# VCA-R2.net
KiCad netlist of a schematic drawn in EAGLE
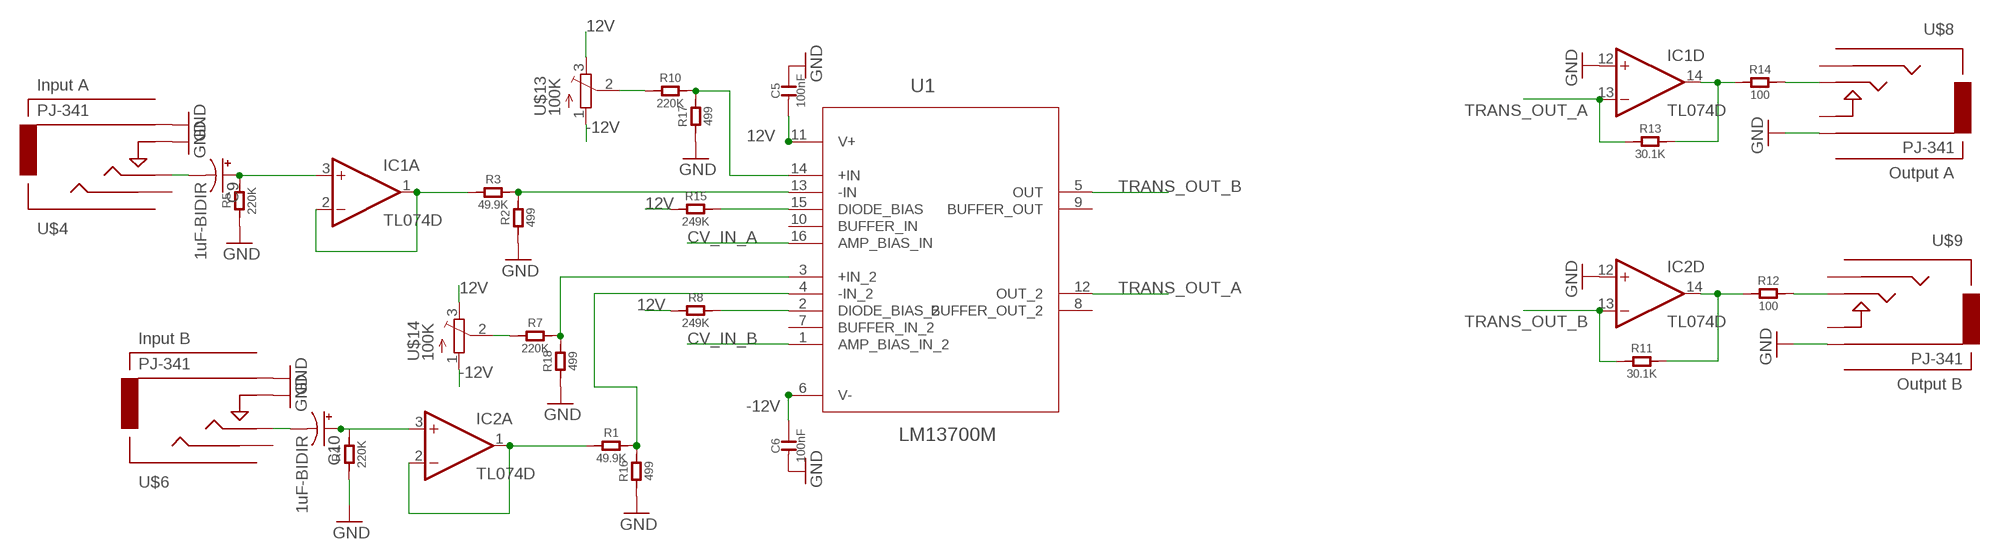
[diagram p0: schematic, sheet 1, part 1 of 2]
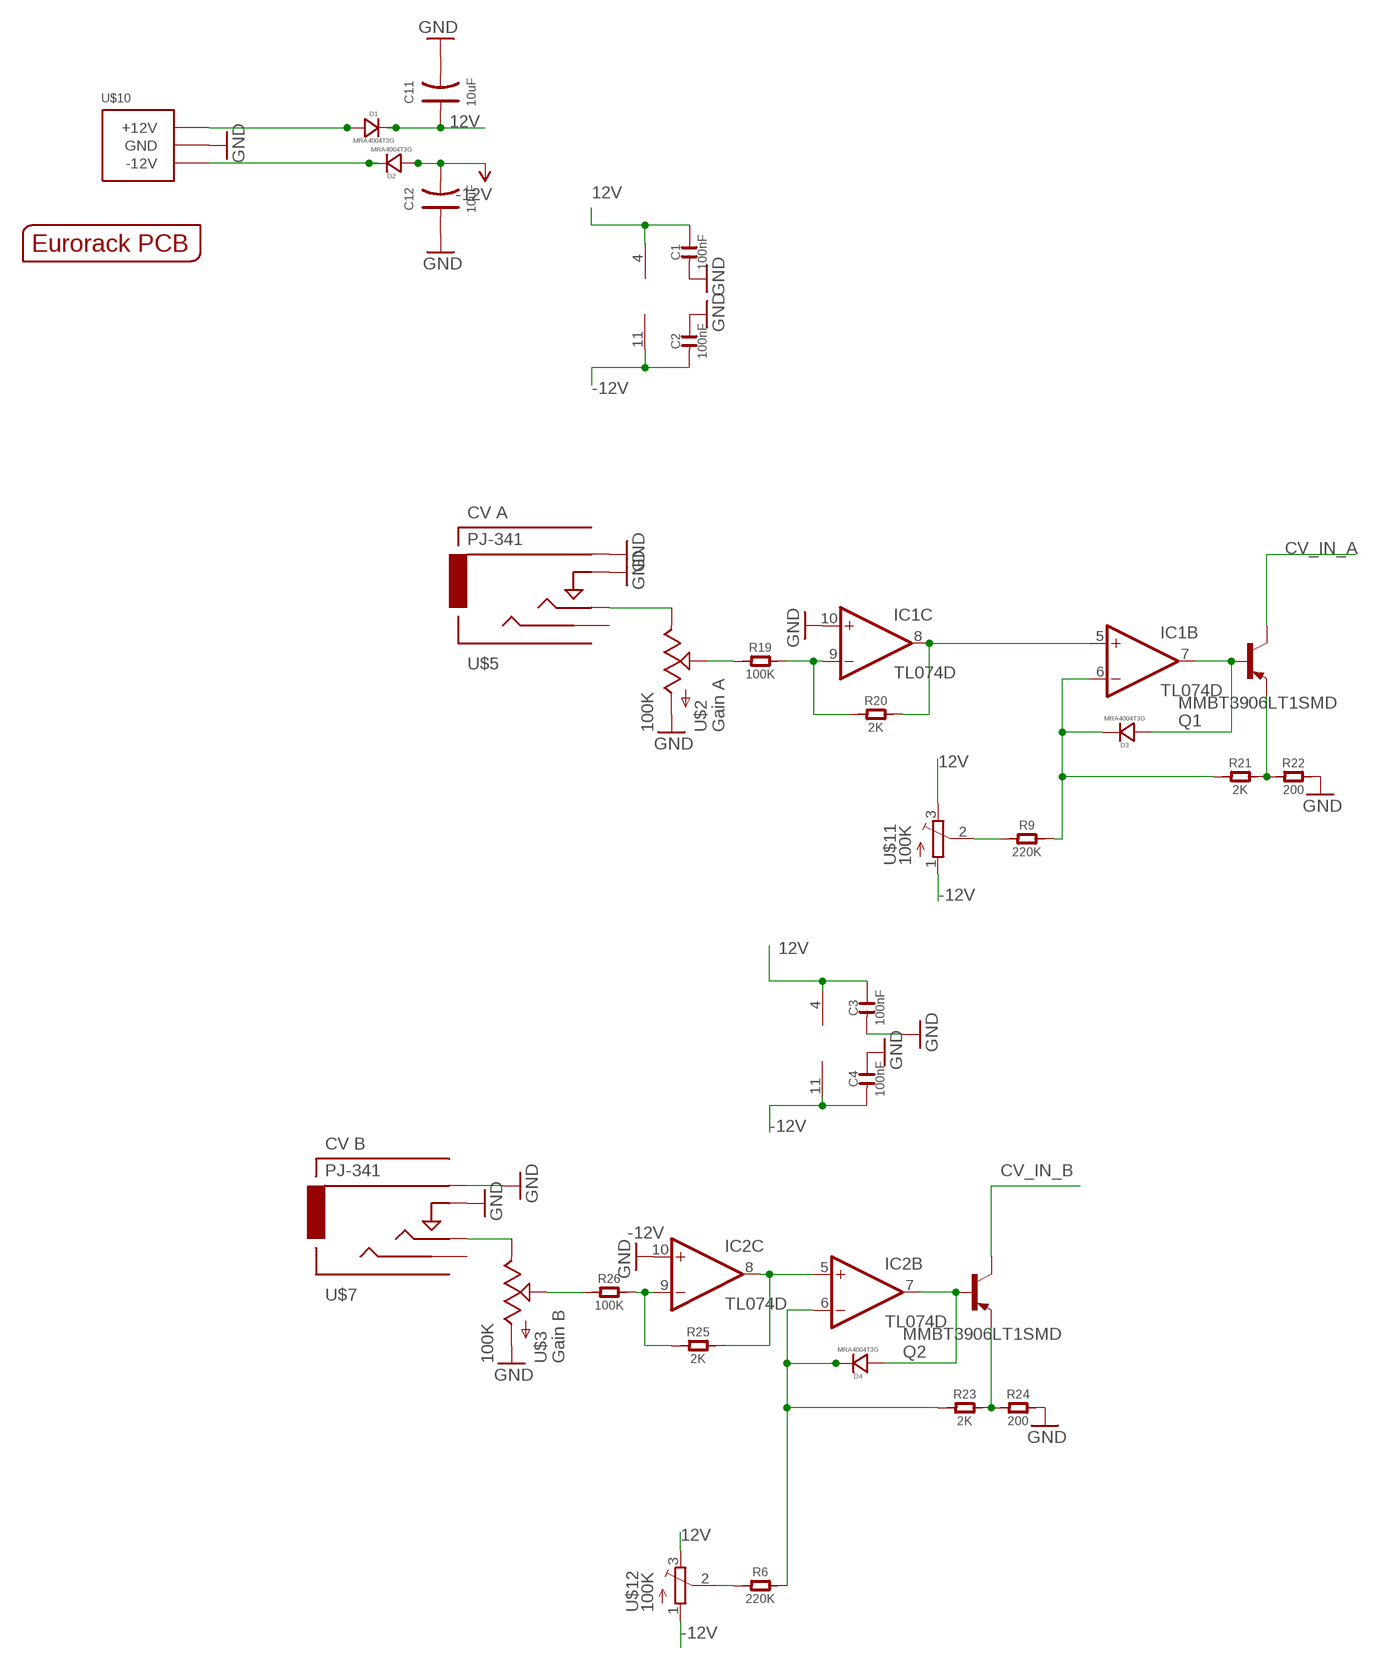
[diagram p1: schematic, sheet 1, part 2 of 2]

(export (version "E")
  (design (tool "Eeschema 10.0.6"))
  (components
    (comp (ref "C1")
      (value "100nF")
      (footprint "eagle-import:C0603")
      (libsource (lib "eagle-import") (part "C-0603"))
    )
    (comp (ref "C2")
      (value "100nF")
      (footprint "eagle-import:C0603")
      (libsource (lib "eagle-import") (part "C-0603"))
    )
    (comp (ref "C3")
      (value "100nF")
      (footprint "eagle-import:C0603")
      (libsource (lib "eagle-import") (part "C-0603"))
    )
    (comp (ref "C4")
      (value "100nF")
      (footprint "eagle-import:C0603")
      (libsource (lib "eagle-import") (part "C-0603"))
    )
    (comp (ref "C5")
      (value "100nF")
      (footprint "eagle-import:C0603")
      (libsource (lib "eagle-import") (part "C-0603"))
    )
    (comp (ref "C6")
      (value "100nF")
      (footprint "eagle-import:C0603")
      (libsource (lib "eagle-import") (part "C-0603"))
    )
    (comp (ref "C9")
      (value "1uF-BIDIR")
      (footprint "eagle-import:153CLV-0505")
      (libsource (lib "eagle-import") (part "CPOL-US153CLV-0505"))
    )
    (comp (ref "C10")
      (value "1uF-BIDIR")
      (footprint "eagle-import:153CLV-0505")
      (libsource (lib "eagle-import") (part "CPOL-US153CLV-0505"))
    )
    (comp (ref "C11")
      (value "10uF")
      (footprint "eagle-import:AVX-A")
      (libsource (lib "eagle-import") (part "C-POLAR-A"))
    )
    (comp (ref "C12")
      (value "10uF")
      (footprint "eagle-import:AVX-A")
      (libsource (lib "eagle-import") (part "C-POLAR-A"))
    )
    (comp (ref "D1")
      (value "MRA4004T3G")
      (footprint "eagle-import:DO-214AC")
      (fields (field (name "MF") "VISHAY") (field (name "MPN") "US1G-E3/5AT"))
      (libsource (lib "eagle-import") (part "D-SMA"))
    )
    (comp (ref "D2")
      (value "MRA4004T3G")
      (footprint "eagle-import:DO-214AC")
      (fields (field (name "MF") "VISHAY") (field (name "MPN") "US1G-E3/5AT"))
      (libsource (lib "eagle-import") (part "D-SMA"))
    )
    (comp (ref "D3")
      (value "MRA4004T3G")
      (footprint "eagle-import:DO-214AC")
      (fields (field (name "MF") "VISHAY") (field (name "MPN") "US1G-E3/5AT"))
      (libsource (lib "eagle-import") (part "D-SMA"))
    )
    (comp (ref "D4")
      (value "MRA4004T3G")
      (footprint "eagle-import:DO-214AC")
      (fields (field (name "MF") "VISHAY") (field (name "MPN") "US1G-E3/5AT"))
      (libsource (lib "eagle-import") (part "D-SMA"))
    )
    (comp (ref "IC1")
      (value "TL074D")
      (footprint "eagle-import:SO14")
      (libsource (lib "eagle-import") (part "TL074D"))
    )
    (comp (ref "IC2")
      (value "TL074D")
      (footprint "eagle-import:SO14")
      (libsource (lib "eagle-import") (part "TL074D"))
    )
    (comp (ref "Q1")
      (value "MMBT3906LT1SMD")
      (footprint "eagle-import:SOT23-BEC")
      (libsource (lib "eagle-import") (part "MMBT3906SMDLT1"))
    )
    (comp (ref "Q2")
      (value "MMBT3906LT1SMD")
      (footprint "eagle-import:SOT23-BEC")
      (libsource (lib "eagle-import") (part "MMBT3906SMDLT1"))
    )
    (comp (ref "R1")
      (value "49.9K")
      (footprint "eagle-import:C0805")
      (libsource (lib "eagle-import") (part "R"))
    )
    (comp (ref "R2")
      (value "499")
      (footprint "eagle-import:C0805")
      (libsource (lib "eagle-import") (part "R"))
    )
    (comp (ref "R3")
      (value "49.9K")
      (footprint "eagle-import:C0805")
      (libsource (lib "eagle-import") (part "R"))
    )
    (comp (ref "R4")
      (value "220K")
      (footprint "eagle-import:C0805")
      (libsource (lib "eagle-import") (part "R"))
    )
    (comp (ref "R5")
      (value "220K")
      (footprint "eagle-import:C0805")
      (libsource (lib "eagle-import") (part "R"))
    )
    (comp (ref "R6")
      (value "220K")
      (footprint "eagle-import:C0805")
      (libsource (lib "eagle-import") (part "R"))
    )
    (comp (ref "R7")
      (value "220K")
      (footprint "eagle-import:C0805")
      (libsource (lib "eagle-import") (part "R"))
    )
    (comp (ref "R8")
      (value "249K")
      (footprint "eagle-import:C0805")
      (libsource (lib "eagle-import") (part "R"))
    )
    (comp (ref "R9")
      (value "220K")
      (footprint "eagle-import:C0805")
      (libsource (lib "eagle-import") (part "R"))
    )
    (comp (ref "R10")
      (value "220K")
      (footprint "eagle-import:C0805")
      (libsource (lib "eagle-import") (part "R"))
    )
    (comp (ref "R11")
      (value "30.1K")
      (footprint "eagle-import:C0805")
      (libsource (lib "eagle-import") (part "R"))
    )
    (comp (ref "R12")
      (value "100")
      (footprint "eagle-import:C0805")
      (libsource (lib "eagle-import") (part "R"))
    )
    (comp (ref "R13")
      (value "30.1K")
      (footprint "eagle-import:C0805")
      (libsource (lib "eagle-import") (part "R"))
    )
    (comp (ref "R14")
      (value "100")
      (footprint "eagle-import:C0805")
      (libsource (lib "eagle-import") (part "R"))
    )
    (comp (ref "R15")
      (value "249K")
      (footprint "eagle-import:C0805")
      (libsource (lib "eagle-import") (part "R"))
    )
    (comp (ref "R16")
      (value "499")
      (footprint "eagle-import:C0805")
      (libsource (lib "eagle-import") (part "R"))
    )
    (comp (ref "R17")
      (value "499")
      (footprint "eagle-import:C0805")
      (libsource (lib "eagle-import") (part "R"))
    )
    (comp (ref "R18")
      (value "499")
      (footprint "eagle-import:C0805")
      (libsource (lib "eagle-import") (part "R"))
    )
    (comp (ref "R19")
      (value "100K")
      (footprint "eagle-import:C0805")
      (libsource (lib "eagle-import") (part "R"))
    )
    (comp (ref "R20")
      (value "2K")
      (footprint "eagle-import:C0805")
      (libsource (lib "eagle-import") (part "R"))
    )
    (comp (ref "R21")
      (value "2K")
      (footprint "eagle-import:C0805")
      (libsource (lib "eagle-import") (part "R"))
    )
    (comp (ref "R22")
      (value "200")
      (footprint "eagle-import:C0805")
      (libsource (lib "eagle-import") (part "R"))
    )
    (comp (ref "R23")
      (value "2K")
      (footprint "eagle-import:C0805")
      (libsource (lib "eagle-import") (part "R"))
    )
    (comp (ref "R24")
      (value "200")
      (footprint "eagle-import:C0805")
      (libsource (lib "eagle-import") (part "R"))
    )
    (comp (ref "R25")
      (value "2K")
      (footprint "eagle-import:C0805")
      (libsource (lib "eagle-import") (part "R"))
    )
    (comp (ref "R26")
      (value "100K")
      (footprint "eagle-import:C0805")
      (libsource (lib "eagle-import") (part "R"))
    )
    (comp (ref "U$1")
      (value "EURORACK_PCB4HP")
      (footprint "eagle-import:EURORACK4HPPCB")
      (libsource (lib "eagle-import") (part "EURORACK_PCB4HP"))
    )
    (comp (ref "U$2")
      (value "100K")
      (footprint "eagle-import:OG-POTS_ALPS_POT_VERTICAL")
      (fields (field (name "DESC") "Gain A"))
      (libsource (lib "eagle-import") (part "POTZEPHPOT"))
    )
    (comp (ref "U$3")
      (value "100K")
      (footprint "eagle-import:OG-POTS_ALPS_POT_VERTICAL")
      (fields (field (name "DESC") "Gain B"))
      (libsource (lib "eagle-import") (part "POTZEPHPOT"))
    )
    (comp (ref "U$4")
      (value "PJ-341")
      (footprint "eagle-import:3.5MM-JACK-SWITCH-13MM-INPUT")
      (fields (field (name "DESC") "Input A"))
      (libsource (lib "eagle-import") (part "AUDIO-JACKINPUT"))
    )
    (comp (ref "U$5")
      (value "PJ-341")
      (footprint "eagle-import:3.5MM-JACK-SWITCH-13MM-INPUT")
      (fields (field (name "DESC") "CV A"))
      (libsource (lib "eagle-import") (part "AUDIO-JACKINPUT"))
    )
    (comp (ref "U$6")
      (value "PJ-341")
      (footprint "eagle-import:3.5MM-JACK-SWITCH-13MM-INPUT")
      (fields (field (name "DESC") "Input B"))
      (libsource (lib "eagle-import") (part "AUDIO-JACKINPUT"))
    )
    (comp (ref "U$7")
      (value "PJ-341")
      (footprint "eagle-import:3.5MM-JACK-SWITCH-13MM-INPUT")
      (fields (field (name "DESC") "CV B"))
      (libsource (lib "eagle-import") (part "AUDIO-JACKINPUT"))
    )
    (comp (ref "U$8")
      (value "PJ-341")
      (footprint "eagle-import:3.5MM-JACK-SWITCH-13MM-OUTPUT")
      (fields (field (name "DESC") "Output A"))
      (libsource (lib "eagle-import") (part "AUDIO-JACKOUTPUT"))
    )
    (comp (ref "U$9")
      (value "PJ-341")
      (footprint "eagle-import:3.5MM-JACK-SWITCH-13MM-OUTPUT")
      (fields (field (name "DESC") "Output B"))
      (libsource (lib "eagle-import") (part "AUDIO-JACKOUTPUT"))
    )
    (comp (ref "U$10")
      (value "POWER_SIMPLE10")
      (footprint "eagle-import:POWER_10")
      (libsource (lib "eagle-import") (part "POWER_SIMPLE10"))
    )
    (comp (ref "U$11")
      (value "100K")
      (footprint "eagle-import:TC33X")
      (libsource (lib "eagle-import") (part "TRIMPOTTC33X"))
    )
    (comp (ref "U$12")
      (value "100K")
      (footprint "eagle-import:TC33X")
      (libsource (lib "eagle-import") (part "TRIMPOTTC33X"))
    )
    (comp (ref "U$13")
      (value "100K")
      (footprint "eagle-import:TC33X")
      (libsource (lib "eagle-import") (part "TRIMPOTTC33X"))
    )
    (comp (ref "U$14")
      (value "100K")
      (footprint "eagle-import:TC33X")
      (libsource (lib "eagle-import") (part "TRIMPOTTC33X"))
    )
    (comp (ref "U1")
      (value "LM13700M")
      (footprint "eagle-import:SOIC127P620X175-16N")
      (libsource (lib "eagle-import") (part "LM13700M"))
    )
  )
  (nets
    (net (code "1") (name "-12V") (class "Default")
      (node (ref "C12") (pin "-") (pinfunction "2_-") (pintype "bidirectional"))
      (node (ref "C2") (pin "1") (pinfunction "1_1") (pintype "bidirectional"))
      (node (ref "C4") (pin "1") (pinfunction "1_1") (pintype "bidirectional"))
      (node (ref "C6") (pin "2") (pinfunction "2_2") (pintype "bidirectional"))
      (node (ref "D2") (pin "1") (pinfunction "+_1") (pintype "passive"))
      (node (ref "IC1") (pin "11") (pinfunction "V-_11") (pintype "power_in"))
      (node (ref "IC2") (pin "11") (pinfunction "V-_11") (pintype "power_in"))
      (node (ref "U$11") (pin "1") (pinfunction "A_1") (pintype "passive"))
      (node (ref "U$12") (pin "1") (pinfunction "A_1") (pintype "passive"))
      (node (ref "U$13") (pin "1") (pinfunction "A_1") (pintype "passive"))
      (node (ref "U$14") (pin "1") (pinfunction "A_1") (pintype "passive"))
      (node (ref "U1") (pin "6") (pinfunction "V-_6") (pintype "power_in"))
    )
    (net (code "2") (name "/12V") (class "Default")
      (node (ref "C1") (pin "2") (pinfunction "2_2") (pintype "bidirectional"))
      (node (ref "C11") (pin "+") (pinfunction "1_+") (pintype "bidirectional"))
      (node (ref "C3") (pin "2") (pinfunction "2_2") (pintype "bidirectional"))
      (node (ref "C5") (pin "1") (pinfunction "1_1") (pintype "bidirectional"))
      (node (ref "D1") (pin "2") (pinfunction "-_2") (pintype "passive"))
      (node (ref "IC1") (pin "4") (pinfunction "V+_4") (pintype "power_in"))
      (node (ref "IC2") (pin "4") (pinfunction "V+_4") (pintype "power_in"))
      (node (ref "R15") (pin "1") (pinfunction "1_1") (pintype "bidirectional"))
      (node (ref "R8") (pin "1") (pinfunction "1_1") (pintype "bidirectional"))
      (node (ref "U$11") (pin "3") (pinfunction "E_3") (pintype "passive"))
      (node (ref "U$12") (pin "3") (pinfunction "E_3") (pintype "passive"))
      (node (ref "U$13") (pin "3") (pinfunction "E_3") (pintype "passive"))
      (node (ref "U$14") (pin "3") (pinfunction "E_3") (pintype "passive"))
      (node (ref "U1") (pin "11") (pinfunction "V+_11") (pintype "power_in"))
    )
    (net (code "3") (name "/CV_IN_A") (class "Default")
      (node (ref "Q1") (pin "C") (pinfunction "C_C") (pintype "passive"))
      (node (ref "U1") (pin "16") (pinfunction "AMP_BIAS_IN_16") (pintype "input"))
    )
    (net (code "4") (name "/CV_IN_B") (class "Default")
      (node (ref "Q2") (pin "C") (pinfunction "C_C") (pintype "passive"))
      (node (ref "U1") (pin "1") (pinfunction "AMP_BIAS_IN_2_1") (pintype "input"))
    )
    (net (code "5") (name "/TRANS_OUT_A") (class "Default")
      (node (ref "IC1") (pin "13") (pinfunction "-IN_13") (pintype "input"))
      (node (ref "R13") (pin "1") (pinfunction "1_1") (pintype "bidirectional"))
      (node (ref "U1") (pin "12") (pinfunction "OUT_2_12") (pintype "output"))
    )
    (net (code "6") (name "/TRANS_OUT_B") (class "Default")
      (node (ref "IC2") (pin "13") (pinfunction "-IN_13") (pintype "input"))
      (node (ref "R11") (pin "1") (pinfunction "1_1") (pintype "bidirectional"))
      (node (ref "U1") (pin "5") (pinfunction "OUT_5") (pintype "output"))
    )
    (net (code "7") (name "GND") (class "Default")
      (node (ref "C1") (pin "1") (pinfunction "1_1") (pintype "bidirectional"))
      (node (ref "C11") (pin "-") (pinfunction "2_-") (pintype "bidirectional"))
      (node (ref "C12") (pin "+") (pinfunction "1_+") (pintype "bidirectional"))
      (node (ref "C2") (pin "2") (pinfunction "2_2") (pintype "bidirectional"))
      (node (ref "C3") (pin "1") (pinfunction "1_1") (pintype "bidirectional"))
      (node (ref "C4") (pin "2") (pinfunction "2_2") (pintype "bidirectional"))
      (node (ref "C5") (pin "2") (pinfunction "2_2") (pintype "bidirectional"))
      (node (ref "C6") (pin "1") (pinfunction "1_1") (pintype "bidirectional"))
      (node (ref "IC1") (pin "10") (pinfunction "+IN_10") (pintype "input"))
      (node (ref "IC1") (pin "12") (pinfunction "+IN_12") (pintype "input"))
      (node (ref "IC2") (pin "10") (pinfunction "+IN_10") (pintype "input"))
      (node (ref "IC2") (pin "12") (pinfunction "+IN_12") (pintype "input"))
      (node (ref "R16") (pin "1") (pinfunction "1_1") (pintype "bidirectional"))
      (node (ref "R17") (pin "1") (pinfunction "1_1") (pintype "bidirectional"))
      (node (ref "R18") (pin "1") (pinfunction "1_1") (pintype "bidirectional"))
      (node (ref "R2") (pin "1") (pinfunction "1_1") (pintype "bidirectional"))
      (node (ref "R22") (pin "2") (pinfunction "2_2") (pintype "bidirectional"))
      (node (ref "R24") (pin "2") (pinfunction "2_2") (pintype "bidirectional"))
      (node (ref "R4") (pin "1") (pinfunction "1_1") (pintype "bidirectional"))
      (node (ref "R5") (pin "1") (pinfunction "1_1") (pintype "bidirectional"))
      (node (ref "U$10") (pin "3") (pinfunction "GND_3") (pintype "bidirectional"))
      (node (ref "U$10") (pin "4") (pinfunction "GND_4") (pintype "bidirectional"))
      (node (ref "U$10") (pin "5") (pinfunction "GND_5") (pintype "bidirectional"))
      (node (ref "U$10") (pin "6") (pinfunction "GND_6") (pintype "bidirectional"))
      (node (ref "U$10") (pin "7") (pinfunction "GND_7") (pintype "bidirectional"))
      (node (ref "U$10") (pin "8") (pinfunction "GND_8") (pintype "bidirectional"))
      (node (ref "U$2") (pin "P$3") (pinfunction "A_P$3") (pintype "passive"))
      (node (ref "U$3") (pin "P$3") (pinfunction "A_P$3") (pintype "passive"))
      (node (ref "U$4") (pin "RING@3") (pinfunction "RING_RING@3") (pintype "bidirectional"))
      (node (ref "U$4") (pin "SWITCH@3") (pinfunction "SWITCH_SWITCH@3") (pintype "bidirectional"))
      (node (ref "U$5") (pin "RING@3") (pinfunction "RING_RING@3") (pintype "bidirectional"))
      (node (ref "U$5") (pin "SWITCH@3") (pinfunction "SWITCH_SWITCH@3") (pintype "bidirectional"))
      (node (ref "U$6") (pin "RING@3") (pinfunction "RING_RING@3") (pintype "bidirectional"))
      (node (ref "U$6") (pin "SWITCH@3") (pinfunction "SWITCH_SWITCH@3") (pintype "bidirectional"))
      (node (ref "U$7") (pin "RING@3") (pinfunction "RING_RING@3") (pintype "bidirectional"))
      (node (ref "U$7") (pin "SWITCH@3") (pinfunction "SWITCH_SWITCH@3") (pintype "bidirectional"))
      (node (ref "U$8") (pin "RING@3") (pinfunction "RING_RING@3") (pintype "bidirectional"))
      (node (ref "U$9") (pin "RING@3") (pinfunction "RING_RING@3") (pintype "bidirectional"))
    )
    (net (code "8") (name "Net-(D1-+)") (class "Default")
      (node (ref "D1") (pin "1") (pinfunction "+_1") (pintype "passive"))
      (node (ref "U$10") (pin "10") (pinfunction "+12V_10") (pintype "bidirectional"))
      (node (ref "U$10") (pin "9") (pinfunction "+12V_9") (pintype "bidirectional"))
    )
    (net (code "9") (name "Net-(D2--)") (class "Default")
      (node (ref "D2") (pin "2") (pinfunction "-_2") (pintype "passive"))
      (node (ref "U$10") (pin "1") (pinfunction "-12V_1") (pintype "bidirectional"))
      (node (ref "U$10") (pin "2") (pinfunction "-12V_2") (pintype "bidirectional"))
    )
    (net (code "10") (name "Net-(D3-+)") (class "Default")
      (node (ref "D3") (pin "1") (pinfunction "+_1") (pintype "passive"))
      (node (ref "IC1") (pin "7") (pinfunction "OUT_7") (pintype "output"))
      (node (ref "Q1") (pin "B") (pinfunction "B_B") (pintype "passive"))
    )
    (net (code "11") (name "Net-(D3--)") (class "Default")
      (node (ref "D3") (pin "2") (pinfunction "-_2") (pintype "passive"))
      (node (ref "IC1") (pin "6") (pinfunction "-IN_6") (pintype "input"))
      (node (ref "R21") (pin "1") (pinfunction "1_1") (pintype "bidirectional"))
      (node (ref "R9") (pin "2") (pinfunction "2_2") (pintype "bidirectional"))
    )
    (net (code "12") (name "Net-(D4-+)") (class "Default")
      (node (ref "D4") (pin "1") (pinfunction "+_1") (pintype "passive"))
      (node (ref "IC2") (pin "7") (pinfunction "OUT_7") (pintype "output"))
      (node (ref "Q2") (pin "B") (pinfunction "B_B") (pintype "passive"))
    )
    (net (code "13") (name "Net-(D4--)") (class "Default")
      (node (ref "D4") (pin "2") (pinfunction "-_2") (pintype "passive"))
      (node (ref "IC2") (pin "6") (pinfunction "-IN_6") (pintype "input"))
      (node (ref "R23") (pin "1") (pinfunction "1_1") (pintype "bidirectional"))
      (node (ref "R6") (pin "2") (pinfunction "2_2") (pintype "bidirectional"))
    )
    (net (code "14") (name "Net-(IC1A-+IN)") (class "Default")
      (node (ref "C9") (pin "+") (pinfunction "+_+") (pintype "passive"))
      (node (ref "IC1") (pin "3") (pinfunction "+IN_3") (pintype "input"))
      (node (ref "R5") (pin "2") (pinfunction "2_2") (pintype "bidirectional"))
    )
    (net (code "15") (name "Net-(IC1A--IN)") (class "Default")
      (node (ref "IC1") (pin "1") (pinfunction "OUT_1") (pintype "output"))
      (node (ref "IC1") (pin "2") (pinfunction "-IN_2") (pintype "input"))
      (node (ref "R3") (pin "1") (pinfunction "1_1") (pintype "bidirectional"))
    )
    (net (code "16") (name "Net-(IC1B-+IN)") (class "Default")
      (node (ref "IC1") (pin "5") (pinfunction "+IN_5") (pintype "input"))
      (node (ref "IC1") (pin "8") (pinfunction "OUT_8") (pintype "output"))
      (node (ref "R20") (pin "2") (pinfunction "2_2") (pintype "bidirectional"))
    )
    (net (code "17") (name "Net-(IC1C--IN)") (class "Default")
      (node (ref "IC1") (pin "9") (pinfunction "-IN_9") (pintype "input"))
      (node (ref "R19") (pin "2") (pinfunction "2_2") (pintype "bidirectional"))
      (node (ref "R20") (pin "1") (pinfunction "1_1") (pintype "bidirectional"))
    )
    (net (code "18") (name "Net-(IC1D-OUT)") (class "Default")
      (node (ref "IC1") (pin "14") (pinfunction "OUT_14") (pintype "output"))
      (node (ref "R13") (pin "2") (pinfunction "2_2") (pintype "bidirectional"))
      (node (ref "R14") (pin "1") (pinfunction "1_1") (pintype "bidirectional"))
    )
    (net (code "19") (name "Net-(IC2A-+IN)") (class "Default")
      (node (ref "C10") (pin "+") (pinfunction "+_+") (pintype "passive"))
      (node (ref "IC2") (pin "3") (pinfunction "+IN_3") (pintype "input"))
      (node (ref "R4") (pin "2") (pinfunction "2_2") (pintype "bidirectional"))
    )
    (net (code "20") (name "Net-(IC2A--IN)") (class "Default")
      (node (ref "IC2") (pin "1") (pinfunction "OUT_1") (pintype "output"))
      (node (ref "IC2") (pin "2") (pinfunction "-IN_2") (pintype "input"))
      (node (ref "R1") (pin "1") (pinfunction "1_1") (pintype "bidirectional"))
    )
    (net (code "21") (name "Net-(IC2B-+IN)") (class "Default")
      (node (ref "IC2") (pin "5") (pinfunction "+IN_5") (pintype "input"))
      (node (ref "IC2") (pin "8") (pinfunction "OUT_8") (pintype "output"))
      (node (ref "R25") (pin "2") (pinfunction "2_2") (pintype "bidirectional"))
    )
    (net (code "22") (name "Net-(IC2C--IN)") (class "Default")
      (node (ref "IC2") (pin "9") (pinfunction "-IN_9") (pintype "input"))
      (node (ref "R25") (pin "1") (pinfunction "1_1") (pintype "bidirectional"))
      (node (ref "R26") (pin "2") (pinfunction "2_2") (pintype "bidirectional"))
    )
    (net (code "23") (name "Net-(IC2D-OUT)") (class "Default")
      (node (ref "IC2") (pin "14") (pinfunction "OUT_14") (pintype "output"))
      (node (ref "R11") (pin "2") (pinfunction "2_2") (pintype "bidirectional"))
      (node (ref "R12") (pin "1") (pinfunction "1_1") (pintype "bidirectional"))
    )
    (net (code "24") (name "Net-(Q1-PadE)") (class "Default")
      (node (ref "Q1") (pin "E") (pinfunction "E_E") (pintype "passive"))
      (node (ref "R21") (pin "2") (pinfunction "2_2") (pintype "bidirectional"))
      (node (ref "R22") (pin "1") (pinfunction "1_1") (pintype "bidirectional"))
    )
    (net (code "25") (name "Net-(Q2-PadE)") (class "Default")
      (node (ref "Q2") (pin "E") (pinfunction "E_E") (pintype "passive"))
      (node (ref "R23") (pin "2") (pinfunction "2_2") (pintype "bidirectional"))
      (node (ref "R24") (pin "1") (pinfunction "1_1") (pintype "bidirectional"))
    )
    (net (code "26") (name "Net-(U$2-E)") (class "Default")
      (node (ref "U$2") (pin "P$1") (pinfunction "E_P$1") (pintype "passive"))
      (node (ref "U$5") (pin "TIP@3") (pinfunction "TIP_TIP@3") (pintype "bidirectional"))
    )
    (net (code "27") (name "Net-(U$2-S)") (class "Default")
      (node (ref "R19") (pin "1") (pinfunction "1_1") (pintype "bidirectional"))
      (node (ref "U$2") (pin "P$2") (pinfunction "S_P$2") (pintype "passive"))
    )
    (net (code "28") (name "Net-(U$3-E)") (class "Default")
      (node (ref "U$3") (pin "P$1") (pinfunction "E_P$1") (pintype "passive"))
      (node (ref "U$7") (pin "TIP@3") (pinfunction "TIP_TIP@3") (pintype "bidirectional"))
    )
    (net (code "29") (name "Net-(U$3-S)") (class "Default")
      (node (ref "R26") (pin "1") (pinfunction "1_1") (pintype "bidirectional"))
      (node (ref "U$3") (pin "P$2") (pinfunction "S_P$2") (pintype "passive"))
    )
    (net (code "30") (name "Net-(U$4-TIP)") (class "Default")
      (node (ref "C9") (pin "-") (pinfunction "-_-") (pintype "passive"))
      (node (ref "U$4") (pin "TIP@3") (pinfunction "TIP_TIP@3") (pintype "bidirectional"))
    )
    (net (code "31") (name "Net-(U$6-TIP)") (class "Default")
      (node (ref "C10") (pin "-") (pinfunction "-_-") (pintype "passive"))
      (node (ref "U$6") (pin "TIP@3") (pinfunction "TIP_TIP@3") (pintype "bidirectional"))
    )
    (net (code "32") (name "Net-(U$8-TIP)") (class "Default")
      (node (ref "R14") (pin "2") (pinfunction "2_2") (pintype "bidirectional"))
      (node (ref "U$8") (pin "TIP@3") (pinfunction "TIP_TIP@3") (pintype "bidirectional"))
    )
    (net (code "33") (name "Net-(U$9-TIP)") (class "Default")
      (node (ref "R12") (pin "2") (pinfunction "2_2") (pintype "bidirectional"))
      (node (ref "U$9") (pin "TIP@3") (pinfunction "TIP_TIP@3") (pintype "bidirectional"))
    )
    (net (code "34") (name "Net-(U$11-S)") (class "Default")
      (node (ref "R9") (pin "1") (pinfunction "1_1") (pintype "bidirectional"))
      (node (ref "U$11") (pin "2") (pinfunction "S_2") (pintype "passive"))
    )
    (net (code "35") (name "Net-(U$12-S)") (class "Default")
      (node (ref "R6") (pin "1") (pinfunction "1_1") (pintype "bidirectional"))
      (node (ref "U$12") (pin "2") (pinfunction "S_2") (pintype "passive"))
    )
    (net (code "36") (name "Net-(U$13-S)") (class "Default")
      (node (ref "R10") (pin "1") (pinfunction "1_1") (pintype "bidirectional"))
      (node (ref "U$13") (pin "2") (pinfunction "S_2") (pintype "passive"))
    )
    (net (code "37") (name "Net-(U$14-S)") (class "Default")
      (node (ref "R7") (pin "1") (pinfunction "1_1") (pintype "bidirectional"))
      (node (ref "U$14") (pin "2") (pinfunction "S_2") (pintype "passive"))
    )
    (net (code "38") (name "Net-(U1-+IN)") (class "Default")
      (node (ref "R10") (pin "2") (pinfunction "2_2") (pintype "bidirectional"))
      (node (ref "R17") (pin "2") (pinfunction "2_2") (pintype "bidirectional"))
      (node (ref "U1") (pin "14") (pinfunction "+IN_14") (pintype "input"))
    )
    (net (code "39") (name "Net-(U1-+IN_2)") (class "Default")
      (node (ref "R18") (pin "2") (pinfunction "2_2") (pintype "bidirectional"))
      (node (ref "R7") (pin "2") (pinfunction "2_2") (pintype "bidirectional"))
      (node (ref "U1") (pin "3") (pinfunction "+IN_2_3") (pintype "input"))
    )
    (net (code "40") (name "Net-(U1--IN)") (class "Default")
      (node (ref "R2") (pin "2") (pinfunction "2_2") (pintype "bidirectional"))
      (node (ref "R3") (pin "2") (pinfunction "2_2") (pintype "bidirectional"))
      (node (ref "U1") (pin "13") (pinfunction "-IN_13") (pintype "input"))
    )
    (net (code "41") (name "Net-(U1--IN_2)") (class "Default")
      (node (ref "R1") (pin "2") (pinfunction "2_2") (pintype "bidirectional"))
      (node (ref "R16") (pin "2") (pinfunction "2_2") (pintype "bidirectional"))
      (node (ref "U1") (pin "4") (pinfunction "-IN_2_4") (pintype "input"))
    )
    (net (code "42") (name "Net-(U1-DIODE_BIAS)") (class "Default")
      (node (ref "R15") (pin "2") (pinfunction "2_2") (pintype "bidirectional"))
      (node (ref "U1") (pin "15") (pinfunction "DIODE_BIAS_15") (pintype "input"))
    )
    (net (code "43") (name "Net-(U1-DIODE_BIAS_2)") (class "Default")
      (node (ref "R8") (pin "2") (pinfunction "2_2") (pintype "bidirectional"))
      (node (ref "U1") (pin "2") (pinfunction "DIODE_BIAS_2_2") (pintype "input"))
    )
    (net (code "44") (name "unconnected-(U$4-SECOND-PadSECOND@3)") (class "Default")
      (node (ref "U$4") (pin "SECOND@3") (pinfunction "SECOND_SECOND@3") (pintype "bidirectional"))
    )
    (net (code "45") (name "unconnected-(U$5-SECOND-PadSECOND@3)") (class "Default")
      (node (ref "U$5") (pin "SECOND@3") (pinfunction "SECOND_SECOND@3") (pintype "bidirectional"))
    )
    (net (code "46") (name "unconnected-(U$6-SECOND-PadSECOND@3)") (class "Default")
      (node (ref "U$6") (pin "SECOND@3") (pinfunction "SECOND_SECOND@3") (pintype "bidirectional"))
    )
    (net (code "47") (name "unconnected-(U$7-SECOND-PadSECOND@3)") (class "Default")
      (node (ref "U$7") (pin "SECOND@3") (pinfunction "SECOND_SECOND@3") (pintype "bidirectional"))
    )
    (net (code "48") (name "unconnected-(U$8-SECOND-PadSECOND@3)") (class "Default")
      (node (ref "U$8") (pin "SECOND@3") (pinfunction "SECOND_SECOND@3") (pintype "bidirectional"))
    )
    (net (code "49") (name "unconnected-(U$8-SWITCH-PadSWITCH@3)") (class "Default")
      (node (ref "U$8") (pin "SWITCH@3") (pinfunction "SWITCH_SWITCH@3") (pintype "bidirectional"))
    )
    (net (code "50") (name "unconnected-(U$9-SECOND-PadSECOND@3)") (class "Default")
      (node (ref "U$9") (pin "SECOND@3") (pinfunction "SECOND_SECOND@3") (pintype "bidirectional"))
    )
    (net (code "51") (name "unconnected-(U$9-SWITCH-PadSWITCH@3)") (class "Default")
      (node (ref "U$9") (pin "SWITCH@3") (pinfunction "SWITCH_SWITCH@3") (pintype "bidirectional"))
    )
    (net (code "52") (name "unconnected-(U1-BUFFER_IN-Pad10)") (class "Default")
      (node (ref "U1") (pin "10") (pinfunction "BUFFER_IN_10") (pintype "input"))
    )
    (net (code "53") (name "unconnected-(U1-BUFFER_IN_2-Pad7)") (class "Default")
      (node (ref "U1") (pin "7") (pinfunction "BUFFER_IN_2_7") (pintype "input"))
    )
    (net (code "54") (name "unconnected-(U1-BUFFER_OUT-Pad9)") (class "Default")
      (node (ref "U1") (pin "9") (pinfunction "BUFFER_OUT_9") (pintype "output"))
    )
    (net (code "55") (name "unconnected-(U1-BUFFER_OUT_2-Pad8)") (class "Default")
      (node (ref "U1") (pin "8") (pinfunction "BUFFER_OUT_2_8") (pintype "output"))
    )
  )
)
